# Sch.net
KiCad netlist of a schematic drawn in Altium Designer
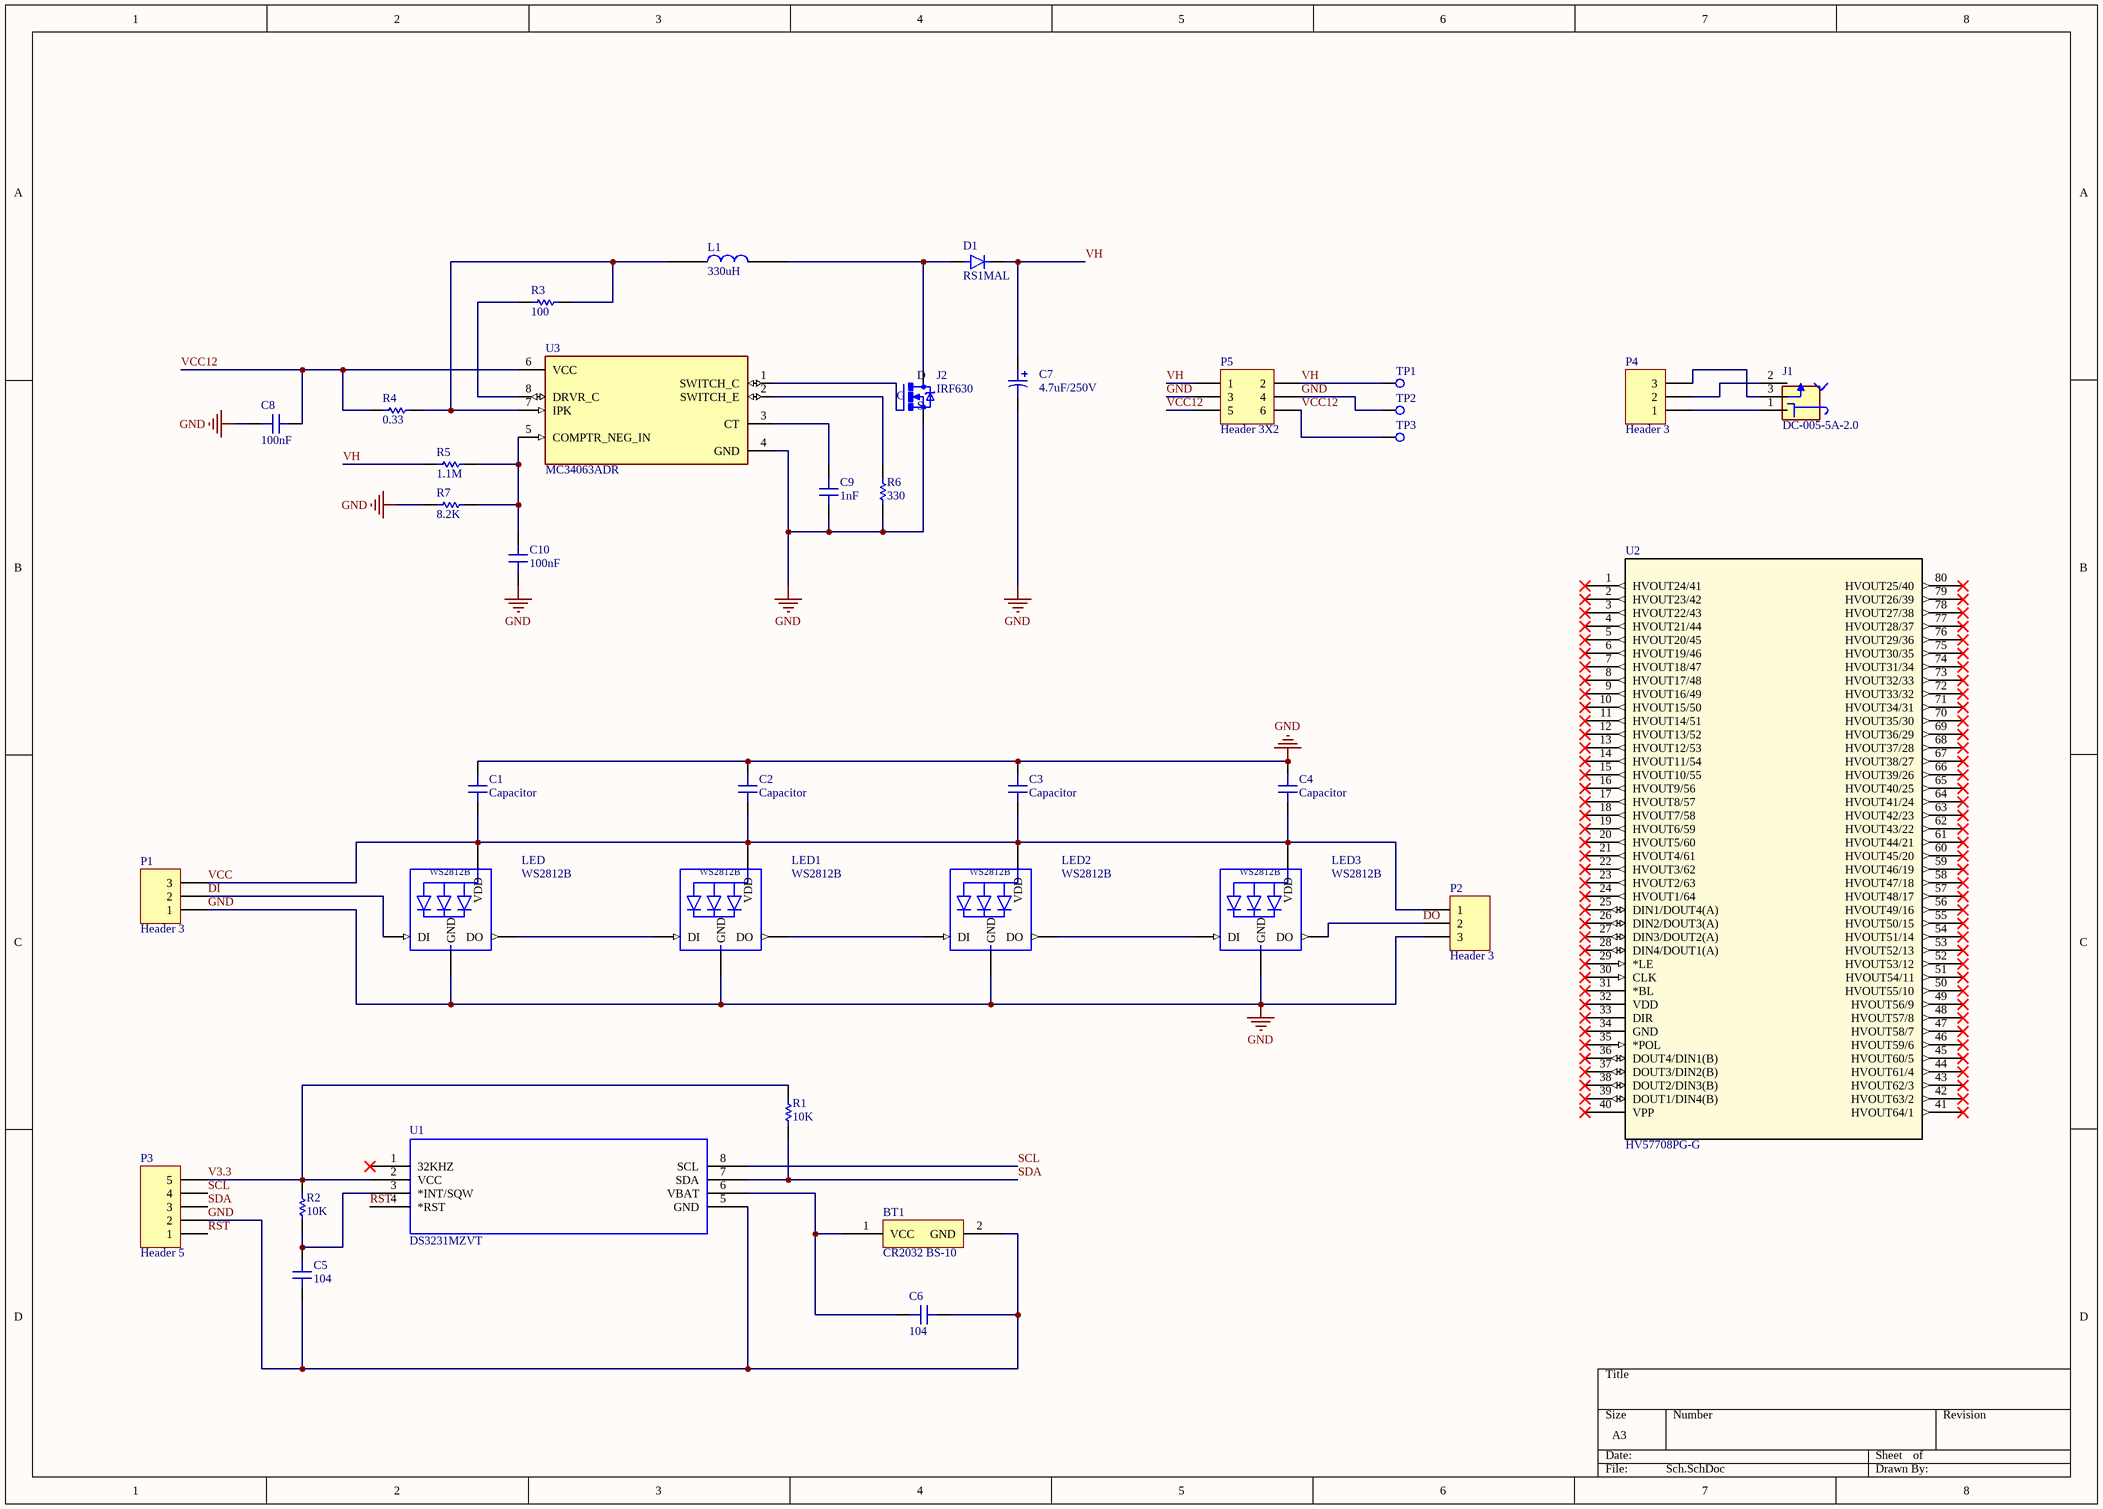
[diagram p0: Sch.SchDoc]

(export (version "E")
  (design (tool "Eeschema 10.0.6"))
  (components
    (comp (ref "BT1")
      (value "CR2032 BS-10")
      (footprint "CR2032 BS-10")
      (libsource (lib "Connector") (part "CR2032 BS-10"))
    )
    (comp (ref "C1") (value "Capacitor") (footprint "0402") (libsource (lib "Basic") (part "Capacitor")))
    (comp (ref "C2") (value "Capacitor") (footprint "0402") (libsource (lib "Basic") (part "Capacitor")))
    (comp (ref "C3") (value "Capacitor") (footprint "0402") (libsource (lib "Basic") (part "Capacitor")))
    (comp (ref "C4") (value "Capacitor") (footprint "0402") (libsource (lib "Basic") (part "Capacitor")))
    (comp (ref "C5") (value "104") (footprint "0805") (libsource (lib "Basic") (part "Capacitor")))
    (comp (ref "C6") (value "104") (footprint "0805") (libsource (lib "Basic") (part "Capacitor")))
    (comp (ref "C7")
      (value "4.7uF/250V")
      (footprint "1808 Polarized")
      (libsource (lib "Basic") (part "CapacitorPolarized"))
    )
    (comp (ref "C8") (value "100nF") (footprint "0805") (libsource (lib "Basic") (part "Capacitor")))
    (comp (ref "C9") (value "1nF") (footprint "0805") (libsource (lib "Basic") (part "Capacitor")))
    (comp (ref "C10") (value "100nF") (footprint "0805") (libsource (lib "Basic") (part "Capacitor")))
    (comp (ref "D1")
      (value "RS1MAL")
      (footprint "SODFL5226X100N")
      (description "1A, 200V - 1000V Fast Recovery Surface Mount Rectifier")
      (fields (field (name "MF") "Taiwan Semiconductor"))
      (libsource (lib "Ic") (part "RS1MAL"))
    )
    (comp (ref "J1")
      (value "DC-005-5A-2.0")
      (footprint "XKB_DC-005-5A-2.0")
      (description "DC Power Receptacle Jack, Through Holeï¼ŒRight Angle")
      (fields (field (name "MF") "XKB Industrial Precision"))
      (libsource (lib "Connector") (part "DC-005-5A-2.0"))
    )
    (comp (ref "J2")
      (value "IRF630")
      (footprint "TO220V")
      (description "N-Channel 200 V 9A (Tc) 30W (Tc) Through Hole TO-220FP")
      (fields (field (name "MF") "STMicroelectronics"))
      (libsource (lib "Ic") (part "IRF630"))
    )
    (comp (ref "L1") (value "330uH") (footprint "INDP125125X80N") (libsource (lib "Basic") (part "Inductor")))
    (comp (ref "LED")
      (value "WS2812B")
      (footprint "WS2812B")
      (description "Raspberry Pi HAT _40 pin_ Wheeled Robotics Kit")
      (fields (field (name "MF") "SparkFun Electronics"))
      (libsource (lib "Ic") (part "WS2812B"))
    )
    (comp (ref "LED1")
      (value "WS2812B")
      (footprint "WS2812B")
      (description "Raspberry Pi HAT _40 pin_ Wheeled Robotics Kit")
      (fields (field (name "MF") "SparkFun Electronics"))
      (libsource (lib "Ic") (part "WS2812B"))
    )
    (comp (ref "LED2")
      (value "WS2812B")
      (footprint "WS2812B")
      (description "Raspberry Pi HAT _40 pin_ Wheeled Robotics Kit")
      (fields (field (name "MF") "SparkFun Electronics"))
      (libsource (lib "Ic") (part "WS2812B"))
    )
    (comp (ref "LED3")
      (value "WS2812B")
      (footprint "WS2812B")
      (description "Raspberry Pi HAT _40 pin_ Wheeled Robotics Kit")
      (fields (field (name "MF") "SparkFun Electronics"))
      (libsource (lib "Ic") (part "WS2812B"))
    )
    (comp (ref "P1")
      (value "Header 3")
      (footprint "HDR1X3")
      (description "Header, 3-Pin")
      (fields (field (name "PUBLISHER") "Altium Limited"))
      (libsource (lib "Connector") (part "Header 3"))
    )
    (comp (ref "P2")
      (value "Header 3")
      (footprint "HDR1X3")
      (description "Header, 3-Pin")
      (fields (field (name "PUBLISHER") "Altium Limited"))
      (libsource (lib "") (part "Header 3_1"))
    )
    (comp (ref "P3")
      (value "Header 5")
      (footprint "HDR1X5")
      (description "Header, 5-Pin")
      (fields (field (name "PUBLISHER") "Altium Limited"))
      (libsource (lib "Connector") (part "Header 5"))
    )
    (comp (ref "P4")
      (value "Header 3")
      (footprint "HDR1X3")
      (description "Header, 3-Pin")
      (fields (field (name "PUBLISHER") "Altium Limited"))
      (libsource (lib "Connector") (part "Header 3"))
    )
    (comp (ref "P5")
      (value "Header 3X2")
      (footprint "HDR2X3")
      (description "Header, 3-Pin, Dual row")
      (fields (field (name "PUBLISHER") "Altium Limited"))
      (libsource (lib "Connector") (part "Header 3X2"))
    )
    (comp (ref "R1") (value "10K") (footprint "0805") (libsource (lib "Basic") (part "Resistor")))
    (comp (ref "R2") (value "10K") (footprint "0805") (libsource (lib "Basic") (part "Resistor")))
    (comp (ref "R3") (value "100") (footprint "0805") (libsource (lib "Basic") (part "Resistor")))
    (comp (ref "R4") (value "0.33") (footprint "0805") (libsource (lib "Basic") (part "Resistor")))
    (comp (ref "R5") (value "1.1M") (footprint "0805") (libsource (lib "Basic") (part "Resistor")))
    (comp (ref "R6") (value "330") (footprint "0805") (libsource (lib "Basic") (part "Resistor")))
    (comp (ref "R7") (value "8.2K") (footprint "0805") (libsource (lib "Basic") (part "Resistor")))
    (comp (ref "TP1") (value "~") (footprint "Test-Point-SMD") (libsource (lib "Basic") (part "TestPoint")))
    (comp (ref "TP2") (value "~") (footprint "Test-Point-SMD") (libsource (lib "Basic") (part "TestPoint")))
    (comp (ref "TP3") (value "~") (footprint "Test-Point-SMD") (libsource (lib "Basic") (part "TestPoint")))
    (comp (ref "U1")
      (value "DS3231MZVT")
      (footprint "DS3231")
      (description "Real Time Clock _RTC_ IC Clock/Calendar IÂ²C, 2-Wire Serial 8-SOIC _0.154, 3.90mm Width_")
      (fields
        (field (name "DIGI-KEY_PART_NUMBER") "DS3231MZ/V+TTR-ND")
        (field (name "MF") "Maxim Integrated")
      )
      (libsource (lib "Ic") (part "DS3231MZVT"))
    )
    (comp (ref "U2")
      (value "HV57708PG-G")
      (footprint "HV57708")
      (description "No Description Available")
      (libsource (lib "Ic") (part "HV57708PG-G"))
    )
    (comp (ref "U3")
      (value "MC34063ADR")
      (footprint "MC34063ADR")
      (description "1.5-A Boost/Buck/Inverting Switching Regulator 8-SOIC 0 to 70")
      (libsource (lib "Ic") (part "MC34063ADR"))
    )
  )
  (nets
    (net (code "1") (name "/DI") (class "Default")
      (node (ref "LED") (pin "4-DIN") (pinfunction "DI_4-DIN") (pintype "input"))
      (node (ref "P1") (pin "2") (pinfunction "2_2") (pintype "passive"))
    )
    (net (code "2") (name "/DO") (class "Default")
      (node (ref "LED3") (pin "2-DOUT") (pinfunction "DO_2-DOUT") (pintype "output"))
      (node (ref "P2") (pin "2") (pinfunction "2_2") (pintype "passive"))
    )
    (net (code "3") (name "/RST") (class "Default")
      (node (ref "P3") (pin "1") (pinfunction "1_1") (pintype "passive"))
      (node (ref "U1") (pin "4") (pinfunction "*RST_4") (pintype "passive"))
    )
    (net (code "4") (name "/SCL") (class "Default")
      (node (ref "P3") (pin "4") (pinfunction "4_4") (pintype "passive"))
      (node (ref "U1") (pin "8") (pinfunction "SCL_8") (pintype "passive"))
    )
    (net (code "5") (name "/SDA") (class "Default")
      (node (ref "P3") (pin "3") (pinfunction "3_3") (pintype "passive"))
      (node (ref "R1") (pin "1") (pinfunction "1_1") (pintype "passive"))
      (node (ref "U1") (pin "7") (pinfunction "SDA_7") (pintype "passive"))
    )
    (net (code "6") (name "/V3.3") (class "Default")
      (node (ref "P3") (pin "5") (pinfunction "5_5") (pintype "passive"))
      (node (ref "R1") (pin "2") (pinfunction "2_2") (pintype "passive"))
      (node (ref "R2") (pin "2") (pinfunction "2_2") (pintype "passive"))
      (node (ref "U1") (pin "2") (pinfunction "VCC_2") (pintype "power_in"))
    )
    (net (code "7") (name "/VCC") (class "Default")
      (node (ref "C1") (pin "1") (pinfunction "1_1") (pintype "passive"))
      (node (ref "C2") (pin "1") (pinfunction "1_1") (pintype "passive"))
      (node (ref "C3") (pin "1") (pinfunction "1_1") (pintype "passive"))
      (node (ref "C4") (pin "1") (pinfunction "1_1") (pintype "passive"))
      (node (ref "LED") (pin "1-VDD") (pinfunction "VDD_1-VDD") (pintype "power_in"))
      (node (ref "LED1") (pin "1-VDD") (pinfunction "VDD_1-VDD") (pintype "power_in"))
      (node (ref "LED2") (pin "1-VDD") (pinfunction "VDD_1-VDD") (pintype "power_in"))
      (node (ref "LED3") (pin "1-VDD") (pinfunction "VDD_1-VDD") (pintype "power_in"))
      (node (ref "P1") (pin "3") (pinfunction "3_3") (pintype "passive"))
      (node (ref "P2") (pin "1") (pinfunction "1_1") (pintype "passive"))
    )
    (net (code "8") (name "/VCC12") (class "Default")
      (node (ref "C8") (pin "1") (pinfunction "1_1") (pintype "passive"))
      (node (ref "P5") (pin "5") (pinfunction "5_5") (pintype "passive"))
      (node (ref "P5") (pin "6") (pinfunction "6_6") (pintype "passive"))
      (node (ref "R4") (pin "1") (pinfunction "1_1") (pintype "passive"))
      (node (ref "TP3") (pin "1") (pinfunction "1_1") (pintype "passive"))
      (node (ref "U3") (pin "6") (pinfunction "VCC_6") (pintype "power_in"))
    )
    (net (code "9") (name "/VH") (class "Default")
      (node (ref "C7") (pin "1") (pinfunction "1_1") (pintype "passive"))
      (node (ref "D1") (pin "1") (pinfunction "K_1") (pintype "passive"))
      (node (ref "P5") (pin "1") (pinfunction "1_1") (pintype "passive"))
      (node (ref "P5") (pin "2") (pinfunction "2_2") (pintype "passive"))
      (node (ref "R5") (pin "1") (pinfunction "1_1") (pintype "passive"))
      (node (ref "TP1") (pin "1") (pinfunction "1_1") (pintype "passive"))
    )
    (net (code "10") (name "GND") (class "Default")
      (node (ref "BT1") (pin "2") (pinfunction "GND_2") (pintype "power_in"))
      (node (ref "C1") (pin "2") (pinfunction "2_2") (pintype "passive"))
      (node (ref "C10") (pin "2") (pinfunction "2_2") (pintype "passive"))
      (node (ref "C2") (pin "2") (pinfunction "2_2") (pintype "passive"))
      (node (ref "C3") (pin "2") (pinfunction "2_2") (pintype "passive"))
      (node (ref "C4") (pin "2") (pinfunction "2_2") (pintype "passive"))
      (node (ref "C5") (pin "1") (pinfunction "1_1") (pintype "passive"))
      (node (ref "C6") (pin "1") (pinfunction "1_1") (pintype "passive"))
      (node (ref "C7") (pin "2") (pinfunction "2_2") (pintype "passive"))
      (node (ref "C8") (pin "2") (pinfunction "2_2") (pintype "passive"))
      (node (ref "C9") (pin "1") (pinfunction "1_1") (pintype "passive"))
      (node (ref "J2") (pin "3") (pinfunction "S_3") (pintype "passive"))
      (node (ref "LED") (pin "3-GND") (pinfunction "GND_3-GND") (pintype "power_in"))
      (node (ref "LED1") (pin "3-GND") (pinfunction "GND_3-GND") (pintype "power_in"))
      (node (ref "LED2") (pin "3-GND") (pinfunction "GND_3-GND") (pintype "power_in"))
      (node (ref "LED3") (pin "3-GND") (pinfunction "GND_3-GND") (pintype "power_in"))
      (node (ref "P1") (pin "1") (pinfunction "1_1") (pintype "passive"))
      (node (ref "P2") (pin "3") (pinfunction "3_3") (pintype "passive"))
      (node (ref "P3") (pin "2") (pinfunction "2_2") (pintype "passive"))
      (node (ref "P5") (pin "3") (pinfunction "3_3") (pintype "passive"))
      (node (ref "P5") (pin "4") (pinfunction "4_4") (pintype "passive"))
      (node (ref "R6") (pin "1") (pinfunction "1_1") (pintype "passive"))
      (node (ref "R7") (pin "1") (pinfunction "1_1") (pintype "passive"))
      (node (ref "TP2") (pin "1") (pinfunction "1_1") (pintype "passive"))
      (node (ref "U1") (pin "5") (pinfunction "GND_5") (pintype "power_in"))
      (node (ref "U3") (pin "4") (pinfunction "GND_4") (pintype "power_in"))
    )
    (net (code "11") (name "Net-(BT1-VCC)") (class "Default")
      (node (ref "BT1") (pin "1") (pinfunction "VCC_1") (pintype "power_in"))
      (node (ref "C6") (pin "2") (pinfunction "2_2") (pintype "passive"))
      (node (ref "U1") (pin "6") (pinfunction "VBAT_6") (pintype "power_in"))
    )
    (net (code "12") (name "Net-(D1-A)") (class "Default")
      (node (ref "D1") (pin "2") (pinfunction "A_2") (pintype "passive"))
      (node (ref "J2") (pin "2") (pinfunction "D_2") (pintype "passive"))
      (node (ref "L1") (pin "2") (pintype "passive"))
    )
    (net (code "13") (name "Net-(J1-Pad1)") (class "Default")
      (node (ref "J1") (pin "1") (pinfunction "1_1") (pintype "passive"))
      (node (ref "P4") (pin "1") (pinfunction "1_1") (pintype "passive"))
    )
    (net (code "14") (name "Net-(J1-Pad2)") (class "Default")
      (node (ref "J1") (pin "2") (pinfunction "2_2") (pintype "passive"))
      (node (ref "P4") (pin "2") (pinfunction "2_2") (pintype "passive"))
    )
    (net (code "15") (name "Net-(J1-Pad3)") (class "Default")
      (node (ref "J1") (pin "3") (pinfunction "3_3") (pintype "passive"))
      (node (ref "P4") (pin "3") (pinfunction "3_3") (pintype "passive"))
    )
    (net (code "16") (name "Net-(J2-G)") (class "Default")
      (node (ref "J2") (pin "1") (pinfunction "G_1") (pintype "passive"))
      (node (ref "U3") (pin "1") (pinfunction "SWITCH_C_1") (pintype "bidirectional"))
    )
    (net (code "17") (name "Net-(LED-DO)") (class "Default")
      (node (ref "LED") (pin "2-DOUT") (pinfunction "DO_2-DOUT") (pintype "output"))
      (node (ref "LED1") (pin "4-DIN") (pinfunction "DI_4-DIN") (pintype "input"))
    )
    (net (code "18") (name "Net-(LED1-DO)") (class "Default")
      (node (ref "LED1") (pin "2-DOUT") (pinfunction "DO_2-DOUT") (pintype "output"))
      (node (ref "LED2") (pin "4-DIN") (pinfunction "DI_4-DIN") (pintype "input"))
    )
    (net (code "19") (name "Net-(LED2-DO)") (class "Default")
      (node (ref "LED2") (pin "2-DOUT") (pinfunction "DO_2-DOUT") (pintype "output"))
      (node (ref "LED3") (pin "4-DIN") (pinfunction "DI_4-DIN") (pintype "input"))
    )
    (net (code "20") (name "Net-(U1-*INT{slash}SQW)") (class "Default")
      (node (ref "C5") (pin "2") (pinfunction "2_2") (pintype "passive"))
      (node (ref "R2") (pin "1") (pinfunction "1_1") (pintype "passive"))
      (node (ref "U1") (pin "3") (pinfunction "*INT/SQW_3") (pintype "passive"))
    )
    (net (code "21") (name "Net-(U3-COMPTR_NEG_IN)") (class "Default")
      (node (ref "C10") (pin "1") (pinfunction "1_1") (pintype "passive"))
      (node (ref "R5") (pin "2") (pinfunction "2_2") (pintype "passive"))
      (node (ref "R7") (pin "2") (pinfunction "2_2") (pintype "passive"))
      (node (ref "U3") (pin "5") (pinfunction "COMPTR_NEG_IN_5") (pintype "input"))
    )
    (net (code "22") (name "Net-(U3-CT)") (class "Default")
      (node (ref "C9") (pin "2") (pinfunction "2_2") (pintype "passive"))
      (node (ref "U3") (pin "3") (pinfunction "CT_3") (pintype "passive"))
    )
    (net (code "23") (name "Net-(U3-DRVR_C)") (class "Default")
      (node (ref "R3") (pin "1") (pinfunction "1_1") (pintype "passive"))
      (node (ref "U3") (pin "8") (pinfunction "DRVR_C_8") (pintype "bidirectional"))
    )
    (net (code "24") (name "Net-(U3-IPK)") (class "Default")
      (node (ref "L1") (pin "1") (pintype "passive"))
      (node (ref "R3") (pin "2") (pinfunction "2_2") (pintype "passive"))
      (node (ref "R4") (pin "2") (pinfunction "2_2") (pintype "passive"))
      (node (ref "U3") (pin "7") (pinfunction "IPK_7") (pintype "input"))
    )
    (net (code "25") (name "Net-(U3-SWITCH_E)") (class "Default")
      (node (ref "R6") (pin "2") (pinfunction "2_2") (pintype "passive"))
      (node (ref "U3") (pin "2") (pinfunction "SWITCH_E_2") (pintype "bidirectional"))
    )
    (net (code "26") (name "unconnected-(U1-32KHZ-Pad1)") (class "Default")
      (node (ref "U1") (pin "1") (pinfunction "32KHZ_1") (pintype "passive+no_connect"))
    )
    (net (code "27") (name "unconnected-(U2-*BL-Pad31)") (class "Default")
      (node (ref "U2") (pin "31") (pinfunction "*BL_31") (pintype "passive+no_connect"))
    )
    (net (code "28") (name "unconnected-(U2-*LE-Pad29)") (class "Default")
      (node (ref "U2") (pin "29") (pinfunction "*LE_29") (pintype "input+no_connect"))
    )
    (net (code "29") (name "unconnected-(U2-*POL-Pad35)") (class "Default")
      (node (ref "U2") (pin "35") (pinfunction "*POL_35") (pintype "input+no_connect"))
    )
    (net (code "30") (name "unconnected-(U2-CLK-Pad30)") (class "Default")
      (node (ref "U2") (pin "30") (pinfunction "CLK_30") (pintype "input+no_connect"))
    )
    (net (code "31") (name "unconnected-(U2-DIN1{slash}DOUT4(A)-Pad25)") (class "Default")
      (node (ref "U2") (pin "25") (pinfunction "DIN1/DOUT4(A)_25") (pintype "bidirectional+no_connect"))
    )
    (net (code "32") (name "unconnected-(U2-DIN2{slash}DOUT3(A)-Pad26)") (class "Default")
      (node (ref "U2") (pin "26") (pinfunction "DIN2/DOUT3(A)_26") (pintype "bidirectional+no_connect"))
    )
    (net (code "33") (name "unconnected-(U2-DIN3{slash}DOUT2(A)-Pad27)") (class "Default")
      (node (ref "U2") (pin "27") (pinfunction "DIN3/DOUT2(A)_27") (pintype "bidirectional+no_connect"))
    )
    (net (code "34") (name "unconnected-(U2-DIN4{slash}DOUT1(A)-Pad28)") (class "Default")
      (node (ref "U2") (pin "28") (pinfunction "DIN4/DOUT1(A)_28") (pintype "bidirectional+no_connect"))
    )
    (net (code "35") (name "unconnected-(U2-DIR-Pad33)") (class "Default")
      (node (ref "U2") (pin "33") (pinfunction "DIR_33") (pintype "passive+no_connect"))
    )
    (net (code "36") (name "unconnected-(U2-DOUT1{slash}DIN4(B)-Pad39)") (class "Default")
      (node (ref "U2") (pin "39") (pinfunction "DOUT1/DIN4(B)_39") (pintype "bidirectional+no_connect"))
    )
    (net (code "37") (name "unconnected-(U2-DOUT2{slash}DIN3(B)-Pad38)") (class "Default")
      (node (ref "U2") (pin "38") (pinfunction "DOUT2/DIN3(B)_38") (pintype "bidirectional+no_connect"))
    )
    (net (code "38") (name "unconnected-(U2-DOUT3{slash}DIN2(B)-Pad37)") (class "Default")
      (node (ref "U2") (pin "37") (pinfunction "DOUT3/DIN2(B)_37") (pintype "bidirectional+no_connect"))
    )
    (net (code "39") (name "unconnected-(U2-DOUT4{slash}DIN1(B)-Pad36)") (class "Default")
      (node (ref "U2") (pin "36") (pinfunction "DOUT4/DIN1(B)_36") (pintype "bidirectional+no_connect"))
    )
    (net (code "40") (name "unconnected-(U2-GND-Pad34)") (class "Default")
      (node (ref "U2") (pin "34") (pinfunction "GND_34") (pintype "power_in+no_connect"))
    )
    (net (code "41") (name "unconnected-(U2-HVOUT1{slash}64-Pad24)") (class "Default")
      (node (ref "U2") (pin "24") (pinfunction "HVOUT1/64_24") (pintype "output+no_connect"))
    )
    (net (code "42") (name "unconnected-(U2-HVOUT2{slash}63-Pad23)") (class "Default")
      (node (ref "U2") (pin "23") (pinfunction "HVOUT2/63_23") (pintype "output+no_connect"))
    )
    (net (code "43") (name "unconnected-(U2-HVOUT3{slash}62-Pad22)") (class "Default")
      (node (ref "U2") (pin "22") (pinfunction "HVOUT3/62_22") (pintype "output+no_connect"))
    )
    (net (code "44") (name "unconnected-(U2-HVOUT4{slash}61-Pad21)") (class "Default")
      (node (ref "U2") (pin "21") (pinfunction "HVOUT4/61_21") (pintype "output+no_connect"))
    )
    (net (code "45") (name "unconnected-(U2-HVOUT5{slash}60-Pad20)") (class "Default")
      (node (ref "U2") (pin "20") (pinfunction "HVOUT5/60_20") (pintype "output+no_connect"))
    )
    (net (code "46") (name "unconnected-(U2-HVOUT6{slash}59-Pad19)") (class "Default")
      (node (ref "U2") (pin "19") (pinfunction "HVOUT6/59_19") (pintype "output+no_connect"))
    )
    (net (code "47") (name "unconnected-(U2-HVOUT7{slash}58-Pad18)") (class "Default")
      (node (ref "U2") (pin "18") (pinfunction "HVOUT7/58_18") (pintype "output+no_connect"))
    )
    (net (code "48") (name "unconnected-(U2-HVOUT8{slash}57-Pad17)") (class "Default")
      (node (ref "U2") (pin "17") (pinfunction "HVOUT8/57_17") (pintype "output+no_connect"))
    )
    (net (code "49") (name "unconnected-(U2-HVOUT9{slash}56-Pad16)") (class "Default")
      (node (ref "U2") (pin "16") (pinfunction "HVOUT9/56_16") (pintype "output+no_connect"))
    )
    (net (code "50") (name "unconnected-(U2-HVOUT10{slash}55-Pad15)") (class "Default")
      (node (ref "U2") (pin "15") (pinfunction "HVOUT10/55_15") (pintype "output+no_connect"))
    )
    (net (code "51") (name "unconnected-(U2-HVOUT11{slash}54-Pad14)") (class "Default")
      (node (ref "U2") (pin "14") (pinfunction "HVOUT11/54_14") (pintype "output+no_connect"))
    )
    (net (code "52") (name "unconnected-(U2-HVOUT12{slash}53-Pad13)") (class "Default")
      (node (ref "U2") (pin "13") (pinfunction "HVOUT12/53_13") (pintype "output+no_connect"))
    )
    (net (code "53") (name "unconnected-(U2-HVOUT13{slash}52-Pad12)") (class "Default")
      (node (ref "U2") (pin "12") (pinfunction "HVOUT13/52_12") (pintype "output+no_connect"))
    )
    (net (code "54") (name "unconnected-(U2-HVOUT14{slash}51-Pad11)") (class "Default")
      (node (ref "U2") (pin "11") (pinfunction "HVOUT14/51_11") (pintype "output+no_connect"))
    )
    (net (code "55") (name "unconnected-(U2-HVOUT15{slash}50-Pad10)") (class "Default")
      (node (ref "U2") (pin "10") (pinfunction "HVOUT15/50_10") (pintype "output+no_connect"))
    )
    (net (code "56") (name "unconnected-(U2-HVOUT16{slash}49-Pad9)") (class "Default")
      (node (ref "U2") (pin "9") (pinfunction "HVOUT16/49_9") (pintype "output+no_connect"))
    )
    (net (code "57") (name "unconnected-(U2-HVOUT17{slash}48-Pad8)") (class "Default")
      (node (ref "U2") (pin "8") (pinfunction "HVOUT17/48_8") (pintype "output+no_connect"))
    )
    (net (code "58") (name "unconnected-(U2-HVOUT18{slash}47-Pad7)") (class "Default")
      (node (ref "U2") (pin "7") (pinfunction "HVOUT18/47_7") (pintype "output+no_connect"))
    )
    (net (code "59") (name "unconnected-(U2-HVOUT19{slash}46-Pad6)") (class "Default")
      (node (ref "U2") (pin "6") (pinfunction "HVOUT19/46_6") (pintype "output+no_connect"))
    )
    (net (code "60") (name "unconnected-(U2-HVOUT20{slash}45-Pad5)") (class "Default")
      (node (ref "U2") (pin "5") (pinfunction "HVOUT20/45_5") (pintype "output+no_connect"))
    )
    (net (code "61") (name "unconnected-(U2-HVOUT21{slash}44-Pad4)") (class "Default")
      (node (ref "U2") (pin "4") (pinfunction "HVOUT21/44_4") (pintype "output+no_connect"))
    )
    (net (code "62") (name "unconnected-(U2-HVOUT22{slash}43-Pad3)") (class "Default")
      (node (ref "U2") (pin "3") (pinfunction "HVOUT22/43_3") (pintype "output+no_connect"))
    )
    (net (code "63") (name "unconnected-(U2-HVOUT23{slash}42-Pad2)") (class "Default")
      (node (ref "U2") (pin "2") (pinfunction "HVOUT23/42_2") (pintype "output+no_connect"))
    )
    (net (code "64") (name "unconnected-(U2-HVOUT24{slash}41-Pad1)") (class "Default")
      (node (ref "U2") (pin "1") (pinfunction "HVOUT24/41_1") (pintype "output+no_connect"))
    )
    (net (code "65") (name "unconnected-(U2-HVOUT25{slash}40-Pad80)") (class "Default")
      (node (ref "U2") (pin "80") (pinfunction "HVOUT25/40_80") (pintype "output+no_connect"))
    )
    (net (code "66") (name "unconnected-(U2-HVOUT26{slash}39-Pad79)") (class "Default")
      (node (ref "U2") (pin "79") (pinfunction "HVOUT26/39_79") (pintype "output+no_connect"))
    )
    (net (code "67") (name "unconnected-(U2-HVOUT27{slash}38-Pad78)") (class "Default")
      (node (ref "U2") (pin "78") (pinfunction "HVOUT27/38_78") (pintype "output+no_connect"))
    )
    (net (code "68") (name "unconnected-(U2-HVOUT28{slash}37-Pad77)") (class "Default")
      (node (ref "U2") (pin "77") (pinfunction "HVOUT28/37_77") (pintype "output+no_connect"))
    )
    (net (code "69") (name "unconnected-(U2-HVOUT29{slash}36-Pad76)") (class "Default")
      (node (ref "U2") (pin "76") (pinfunction "HVOUT29/36_76") (pintype "output+no_connect"))
    )
    (net (code "70") (name "unconnected-(U2-HVOUT30{slash}35-Pad75)") (class "Default")
      (node (ref "U2") (pin "75") (pinfunction "HVOUT30/35_75") (pintype "output+no_connect"))
    )
    (net (code "71") (name "unconnected-(U2-HVOUT31{slash}34-Pad74)") (class "Default")
      (node (ref "U2") (pin "74") (pinfunction "HVOUT31/34_74") (pintype "output+no_connect"))
    )
    (net (code "72") (name "unconnected-(U2-HVOUT32{slash}33-Pad73)") (class "Default")
      (node (ref "U2") (pin "73") (pinfunction "HVOUT32/33_73") (pintype "output+no_connect"))
    )
    (net (code "73") (name "unconnected-(U2-HVOUT33{slash}32-Pad72)") (class "Default")
      (node (ref "U2") (pin "72") (pinfunction "HVOUT33/32_72") (pintype "output+no_connect"))
    )
    (net (code "74") (name "unconnected-(U2-HVOUT34{slash}31-Pad71)") (class "Default")
      (node (ref "U2") (pin "71") (pinfunction "HVOUT34/31_71") (pintype "output+no_connect"))
    )
    (net (code "75") (name "unconnected-(U2-HVOUT35{slash}30-Pad70)") (class "Default")
      (node (ref "U2") (pin "70") (pinfunction "HVOUT35/30_70") (pintype "output+no_connect"))
    )
    (net (code "76") (name "unconnected-(U2-HVOUT36{slash}29-Pad69)") (class "Default")
      (node (ref "U2") (pin "69") (pinfunction "HVOUT36/29_69") (pintype "output+no_connect"))
    )
    (net (code "77") (name "unconnected-(U2-HVOUT37{slash}28-Pad68)") (class "Default")
      (node (ref "U2") (pin "68") (pinfunction "HVOUT37/28_68") (pintype "output+no_connect"))
    )
    (net (code "78") (name "unconnected-(U2-HVOUT38{slash}27-Pad67)") (class "Default")
      (node (ref "U2") (pin "67") (pinfunction "HVOUT38/27_67") (pintype "output+no_connect"))
    )
    (net (code "79") (name "unconnected-(U2-HVOUT39{slash}26-Pad66)") (class "Default")
      (node (ref "U2") (pin "66") (pinfunction "HVOUT39/26_66") (pintype "output+no_connect"))
    )
    (net (code "80") (name "unconnected-(U2-HVOUT40{slash}25-Pad65)") (class "Default")
      (node (ref "U2") (pin "65") (pinfunction "HVOUT40/25_65") (pintype "output+no_connect"))
    )
    (net (code "81") (name "unconnected-(U2-HVOUT41{slash}24-Pad64)") (class "Default")
      (node (ref "U2") (pin "64") (pinfunction "HVOUT41/24_64") (pintype "output+no_connect"))
    )
    (net (code "82") (name "unconnected-(U2-HVOUT42{slash}23-Pad63)") (class "Default")
      (node (ref "U2") (pin "63") (pinfunction "HVOUT42/23_63") (pintype "output+no_connect"))
    )
    (net (code "83") (name "unconnected-(U2-HVOUT43{slash}22-Pad62)") (class "Default")
      (node (ref "U2") (pin "62") (pinfunction "HVOUT43/22_62") (pintype "output+no_connect"))
    )
    (net (code "84") (name "unconnected-(U2-HVOUT44{slash}21-Pad61)") (class "Default")
      (node (ref "U2") (pin "61") (pinfunction "HVOUT44/21_61") (pintype "output+no_connect"))
    )
    (net (code "85") (name "unconnected-(U2-HVOUT45{slash}20-Pad60)") (class "Default")
      (node (ref "U2") (pin "60") (pinfunction "HVOUT45/20_60") (pintype "output+no_connect"))
    )
    (net (code "86") (name "unconnected-(U2-HVOUT46{slash}19-Pad59)") (class "Default")
      (node (ref "U2") (pin "59") (pinfunction "HVOUT46/19_59") (pintype "output+no_connect"))
    )
    (net (code "87") (name "unconnected-(U2-HVOUT47{slash}18-Pad58)") (class "Default")
      (node (ref "U2") (pin "58") (pinfunction "HVOUT47/18_58") (pintype "output+no_connect"))
    )
    (net (code "88") (name "unconnected-(U2-HVOUT48{slash}17-Pad57)") (class "Default")
      (node (ref "U2") (pin "57") (pinfunction "HVOUT48/17_57") (pintype "output+no_connect"))
    )
    (net (code "89") (name "unconnected-(U2-HVOUT49{slash}16-Pad56)") (class "Default")
      (node (ref "U2") (pin "56") (pinfunction "HVOUT49/16_56") (pintype "output+no_connect"))
    )
    (net (code "90") (name "unconnected-(U2-HVOUT50{slash}15-Pad55)") (class "Default")
      (node (ref "U2") (pin "55") (pinfunction "HVOUT50/15_55") (pintype "output+no_connect"))
    )
    (net (code "91") (name "unconnected-(U2-HVOUT51{slash}14-Pad54)") (class "Default")
      (node (ref "U2") (pin "54") (pinfunction "HVOUT51/14_54") (pintype "output+no_connect"))
    )
    (net (code "92") (name "unconnected-(U2-HVOUT52{slash}13-Pad53)") (class "Default")
      (node (ref "U2") (pin "53") (pinfunction "HVOUT52/13_53") (pintype "output+no_connect"))
    )
    (net (code "93") (name "unconnected-(U2-HVOUT53{slash}12-Pad52)") (class "Default")
      (node (ref "U2") (pin "52") (pinfunction "HVOUT53/12_52") (pintype "output+no_connect"))
    )
    (net (code "94") (name "unconnected-(U2-HVOUT54{slash}11-Pad51)") (class "Default")
      (node (ref "U2") (pin "51") (pinfunction "HVOUT54/11_51") (pintype "output+no_connect"))
    )
    (net (code "95") (name "unconnected-(U2-HVOUT55{slash}10-Pad50)") (class "Default")
      (node (ref "U2") (pin "50") (pinfunction "HVOUT55/10_50") (pintype "output+no_connect"))
    )
    (net (code "96") (name "unconnected-(U2-HVOUT56{slash}9-Pad49)") (class "Default")
      (node (ref "U2") (pin "49") (pinfunction "HVOUT56/9_49") (pintype "output+no_connect"))
    )
    (net (code "97") (name "unconnected-(U2-HVOUT57{slash}8-Pad48)") (class "Default")
      (node (ref "U2") (pin "48") (pinfunction "HVOUT57/8_48") (pintype "output+no_connect"))
    )
    (net (code "98") (name "unconnected-(U2-HVOUT58{slash}7-Pad47)") (class "Default")
      (node (ref "U2") (pin "47") (pinfunction "HVOUT58/7_47") (pintype "output+no_connect"))
    )
    (net (code "99") (name "unconnected-(U2-HVOUT59{slash}6-Pad46)") (class "Default")
      (node (ref "U2") (pin "46") (pinfunction "HVOUT59/6_46") (pintype "output+no_connect"))
    )
    (net (code "100") (name "unconnected-(U2-HVOUT60{slash}5-Pad45)") (class "Default")
      (node (ref "U2") (pin "45") (pinfunction "HVOUT60/5_45") (pintype "output+no_connect"))
    )
    (net (code "101") (name "unconnected-(U2-HVOUT61{slash}4-Pad44)") (class "Default")
      (node (ref "U2") (pin "44") (pinfunction "HVOUT61/4_44") (pintype "output+no_connect"))
    )
    (net (code "102") (name "unconnected-(U2-HVOUT62{slash}3-Pad43)") (class "Default")
      (node (ref "U2") (pin "43") (pinfunction "HVOUT62/3_43") (pintype "output+no_connect"))
    )
    (net (code "103") (name "unconnected-(U2-HVOUT63{slash}2-Pad42)") (class "Default")
      (node (ref "U2") (pin "42") (pinfunction "HVOUT63/2_42") (pintype "output+no_connect"))
    )
    (net (code "104") (name "unconnected-(U2-HVOUT64{slash}1-Pad41)") (class "Default")
      (node (ref "U2") (pin "41") (pinfunction "HVOUT64/1_41") (pintype "output+no_connect"))
    )
    (net (code "105") (name "unconnected-(U2-VDD-Pad32)") (class "Default")
      (node (ref "U2") (pin "32") (pinfunction "VDD_32") (pintype "power_in+no_connect"))
    )
    (net (code "106") (name "unconnected-(U2-VPP-Pad40)") (class "Default")
      (node (ref "U2") (pin "40") (pinfunction "VPP_40") (pintype "power_in+no_connect"))
    )
  )
)
